# Colibri.net
KiCad netlist of a schematic drawn in Altium Designer
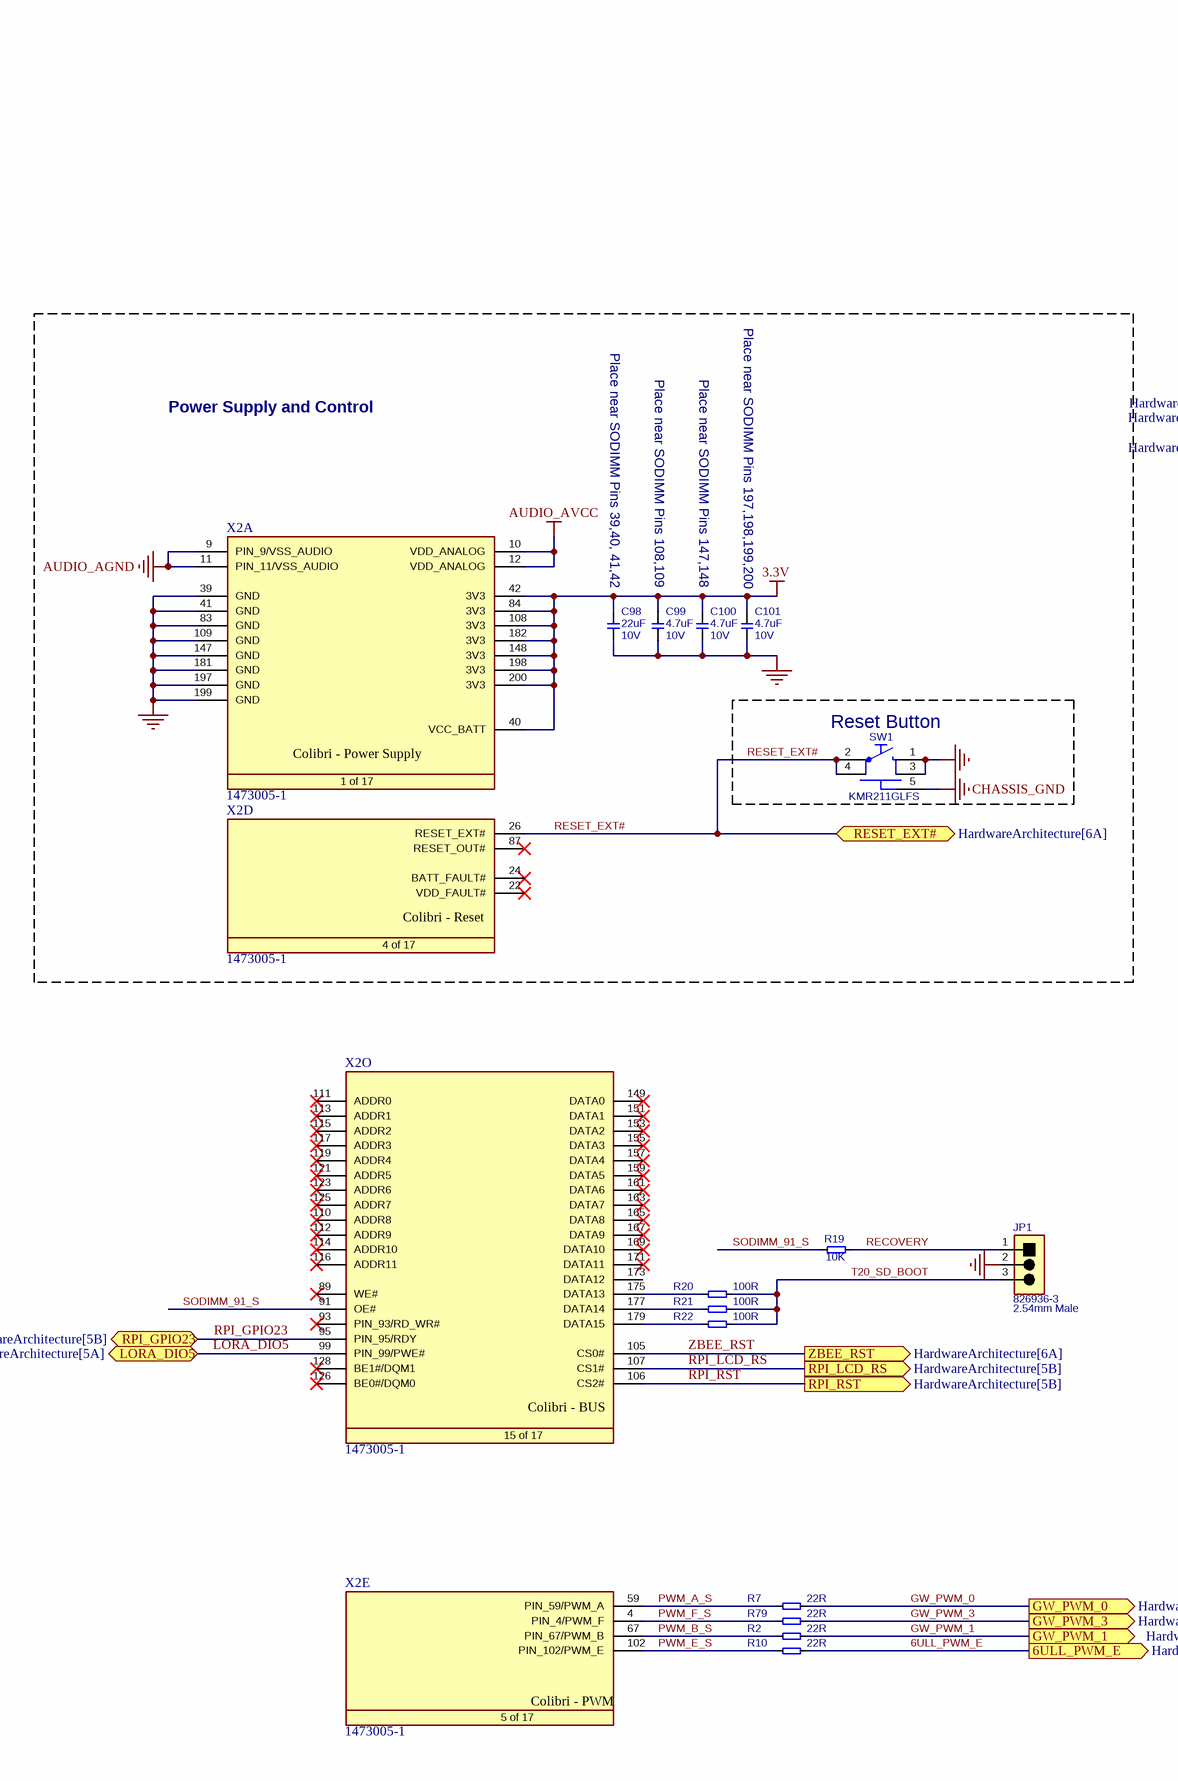
[diagram p0: Colibri.SchDoc, left]
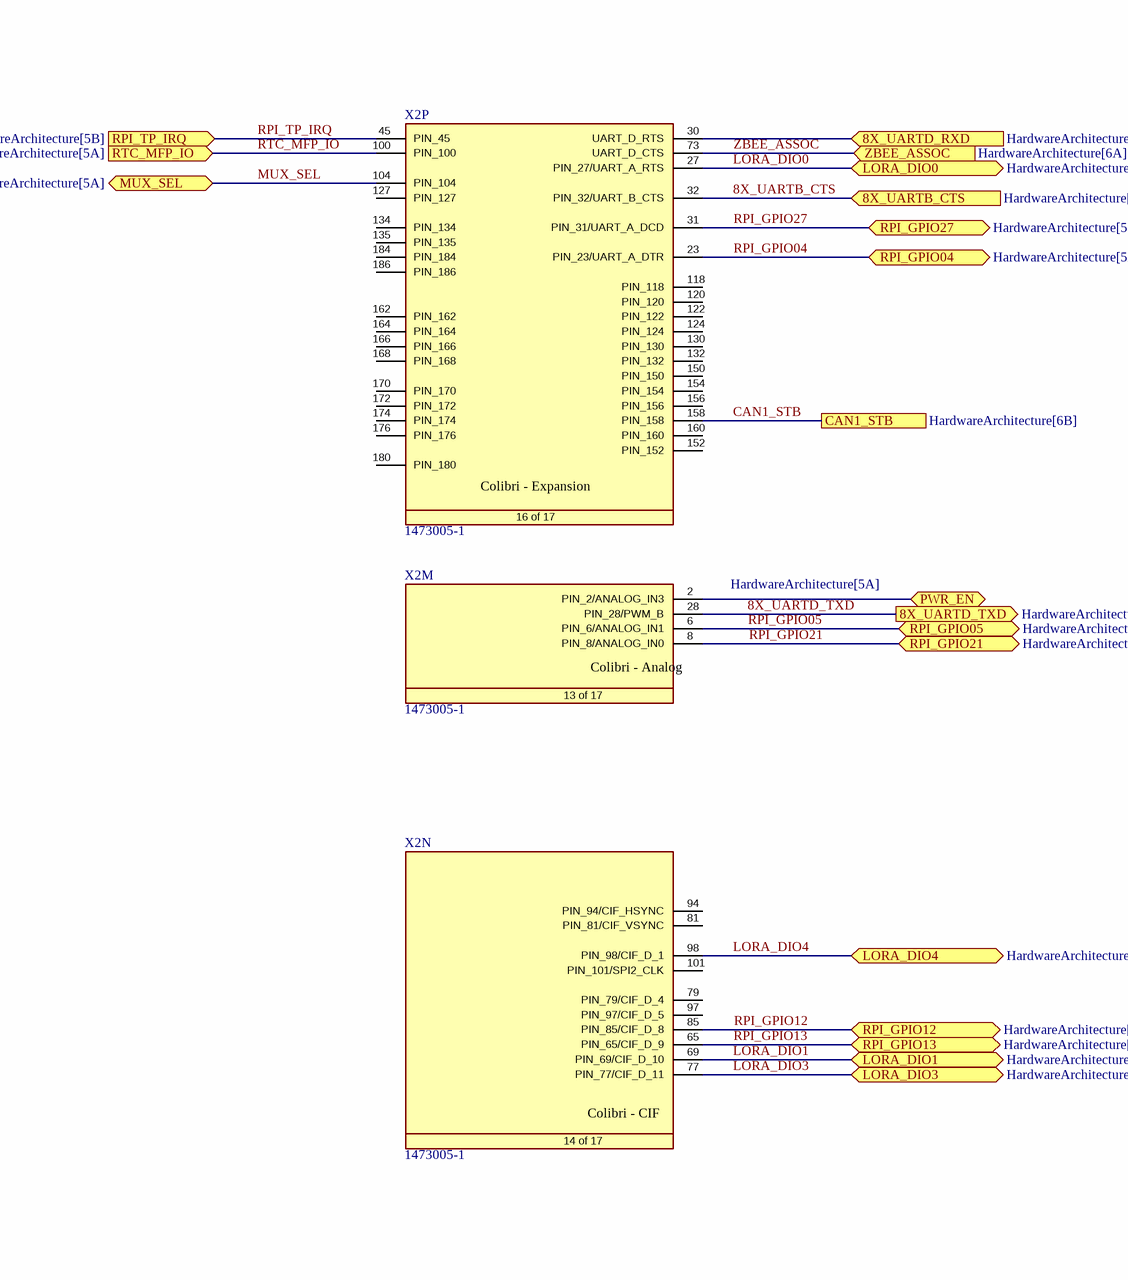
[diagram p1: Colibri.SchDoc, right]

(export (version "E")
  (design (tool "Eeschema 10.0.6"))
  (components
    (comp (ref "C98")
      (value "22uF")
      (footprint "T_CAPC0805X125N")
      (description "Capacitor Ceramic X5R 22uF 10V 20% 0805")
      (fields (field (name "TOLERANCE") "20%") (field (name "RATING") "10V"))
      (libsource (lib "Iris") (part "C-X5R-22uF-10V-20%-0805"))
    )
    (comp (ref "C99")
      (value "4.7uF")
      (footprint "T_CAPC0603X33N")
      (description "Capacitor Ceramic X5R 4.7uF 10V 10% 0603")
      (fields (field (name "TOLERANCE") "10%") (field (name "RATING") "10V"))
      (libsource (lib "Iris") (part "C-X5R-4.7uF-10V-10%-0603"))
    )
    (comp (ref "C100")
      (value "4.7uF")
      (footprint "T_CAPC0603X33N")
      (description "Capacitor Ceramic X5R 4.7uF 10V 10% 0603")
      (fields (field (name "TOLERANCE") "10%") (field (name "RATING") "10V"))
      (libsource (lib "Iris") (part "C-X5R-4.7uF-10V-10%-0603"))
    )
    (comp (ref "C101")
      (value "4.7uF")
      (footprint "T_CAPC0603X33N")
      (description "Capacitor Ceramic X5R 4.7uF 10V 10% 0603")
      (fields (field (name "TOLERANCE") "10%") (field (name "RATING") "10V"))
      (libsource (lib "Iris") (part "C-X5R-4.7uF-10V-10%-0603"))
    )
    (comp (ref "JP1")
      (value "826936-3")
      (footprint "T_TYCO_826936-3")
      (description "Jumper, 3-Pin")
      (fields (field (name "MANUFACTURER PART NO.") "826936-3"))
      (libsource (lib "Iris") (part "CON-Tyco-826936-3-1X3-2.54mm-JP"))
    )
    (comp (ref "R2")
      (value "22R")
      (footprint "RESC1005X40N")
      (description "Resistor 22 ohm 63mW 5% 0402")
      (fields (field (name "TOLERANCE") "5%"))
      (libsource (lib "Iris") (part "R-22R-63mW-5%-0402"))
    )
    (comp (ref "R7")
      (value "22R")
      (footprint "RESC1005X40N")
      (description "Resistor 22 ohm 63mW 5% 0402")
      (fields (field (name "TOLERANCE") "5%"))
      (libsource (lib "Iris") (part "R-22R-63mW-5%-0402"))
    )
    (comp (ref "R10")
      (value "22R")
      (footprint "RESC1005X40N")
      (description "Resistor 22 ohm 63mW 5% 0402")
      (fields (field (name "TOLERANCE") "5%"))
      (libsource (lib "Iris") (part "R-22R-63mW-5%-0402"))
    )
    (comp (ref "R19")
      (value "10K")
      (footprint "RESC1005X40N")
      (description "Resistor 10 Kohm 63mW 1% 0402")
      (fields (field (name "TOLERANCE") "1%"))
      (libsource (lib "Iris") (part "R-10KR-63mW-1%-0402"))
    )
    (comp (ref "R20")
      (value "100R")
      (footprint "T_RESC0603X30N")
      (description "Resistor 100 ohm 63mW 5% 0603")
      (fields (field (name "TOLERANCE") "5%"))
      (libsource (lib "Iris") (part "R-100R-63mW-5%-0603"))
    )
    (comp (ref "R21")
      (value "100R")
      (footprint "T_RESC0603X30N")
      (description "Resistor 100 ohm 63mW 5% 0603")
      (fields (field (name "TOLERANCE") "5%"))
      (libsource (lib "Iris") (part "R-100R-63mW-5%-0603"))
    )
    (comp (ref "R22")
      (value "100R")
      (footprint "T_RESC0603X30N")
      (description "Resistor 100 ohm 63mW 5% 0603")
      (fields (field (name "TOLERANCE") "5%"))
      (libsource (lib "Iris") (part "R-100R-63mW-5%-0603"))
    )
    (comp (ref "R79")
      (value "22R")
      (footprint "RESC1005X40N")
      (description "Resistor 22 ohm 63mW 5% 0402")
      (fields (field (name "TOLERANCE") "5%"))
      (libsource (lib "Iris") (part "R-22R-63mW-5%-0402"))
    )
    (comp (ref "SW1")
      (value "KMR211GLFS")
      (footprint "T_CnK_KMR211GLFS")
      (description "Power ON Switch")
      (libsource (lib "Iris") (part "SW_CnK-KMR211GLFS-1VA"))
    )
    (comp (ref "X2")
      (value "1473005-1")
      (footprint "T_Tyco_1473005-1")
      (description "SODIMM Connector")
      (fields (field (name "MANUFACTURER PART NO.") "1473005-1"))
      (libsource (lib "Iris") (part "CON-Tyco-1473005-1-200-0.6mm"))
    )
  )
  (nets
    (net (code "1") (name "/6ULL_PWM_E") (class "Default")
      (node (ref "R10") (pin "2") (pinfunction "2_2") (pintype "passive"))
    )
    (net (code "2") (name "/8X_UARTB_CTS") (class "Default")
      (node (ref "X2") (pin "32") (pinfunction "PIN_32/UART_B_CTS_32") (pintype "passive"))
    )
    (net (code "3") (name "/8X_UARTD_RXD") (class "Default")
      (node (ref "X2") (pin "30") (pinfunction "UART_D_RTS_30") (pintype "passive"))
    )
    (net (code "4") (name "/8X_UARTD_TXD") (class "Default")
      (node (ref "X2") (pin "28") (pinfunction "PIN_28/PWM_B_28") (pintype "passive"))
    )
    (net (code "5") (name "/CAN1_STB") (class "Default")
      (node (ref "X2") (pin "158") (pinfunction "PIN_158_158") (pintype "passive"))
    )
    (net (code "6") (name "/GW_PWM_0") (class "Default")
      (node (ref "R7") (pin "2") (pinfunction "2_2") (pintype "passive"))
    )
    (net (code "7") (name "/GW_PWM_1") (class "Default")
      (node (ref "R2") (pin "2") (pinfunction "2_2") (pintype "passive"))
    )
    (net (code "8") (name "/GW_PWM_3") (class "Default")
      (node (ref "R79") (pin "2") (pinfunction "2_2") (pintype "passive"))
    )
    (net (code "9") (name "/LORA_DIO0") (class "Default")
      (node (ref "X2") (pin "27") (pinfunction "PIN_27/UART_A_RTS_27") (pintype "passive"))
    )
    (net (code "10") (name "/LORA_DIO1") (class "Default")
      (node (ref "X2") (pin "69") (pinfunction "PIN_69/CIF_D_10_69") (pintype "passive"))
    )
    (net (code "11") (name "/LORA_DIO3") (class "Default")
      (node (ref "X2") (pin "77") (pinfunction "PIN_77/CIF_D_11_77") (pintype "passive"))
    )
    (net (code "12") (name "/LORA_DIO4") (class "Default")
      (node (ref "X2") (pin "98") (pinfunction "PIN_98/CIF_D_1_98") (pintype "passive"))
    )
    (net (code "13") (name "/LORA_DIO5") (class "Default")
      (node (ref "X2") (pin "99") (pinfunction "PIN_99/PWE#_99") (pintype "passive"))
    )
    (net (code "14") (name "/MUX_SEL") (class "Default")
      (node (ref "X2") (pin "104") (pinfunction "PIN_104_104") (pintype "passive"))
    )
    (net (code "15") (name "/PWM_A_S") (class "Default")
      (node (ref "R7") (pin "1") (pinfunction "1_1") (pintype "passive"))
      (node (ref "X2") (pin "59") (pinfunction "PIN_59/PWM_A_59") (pintype "passive"))
    )
    (net (code "16") (name "/PWM_B_S") (class "Default")
      (node (ref "R2") (pin "1") (pinfunction "1_1") (pintype "passive"))
      (node (ref "X2") (pin "67") (pinfunction "PIN_67/PWM_B_67") (pintype "passive"))
    )
    (net (code "17") (name "/PWM_E_S") (class "Default")
      (node (ref "R10") (pin "1") (pinfunction "1_1") (pintype "passive"))
      (node (ref "X2") (pin "102") (pinfunction "PIN_102/PWM_E_102") (pintype "passive"))
    )
    (net (code "18") (name "/PWM_F_S") (class "Default")
      (node (ref "R79") (pin "1") (pinfunction "1_1") (pintype "passive"))
      (node (ref "X2") (pin "4") (pinfunction "PIN_4/PWM_F_4") (pintype "passive"))
    )
    (net (code "19") (name "/PWR_EN") (class "Default")
      (node (ref "X2") (pin "2") (pinfunction "PIN_2/ANALOG_IN3_2") (pintype "passive"))
    )
    (net (code "20") (name "/RECOVERY") (class "Default")
      (node (ref "JP1") (pin "1") (pinfunction "1_1") (pintype "passive"))
      (node (ref "R19") (pin "2") (pinfunction "2_2") (pintype "passive"))
    )
    (net (code "21") (name "/RESET_EXT#") (class "Default")
      (node (ref "SW1") (pin "2") (pinfunction "2_2") (pintype "passive"))
      (node (ref "SW1") (pin "4") (pinfunction "4_4") (pintype "passive"))
      (node (ref "X2") (pin "26") (pinfunction "RESET_EXT#_26") (pintype "passive"))
    )
    (net (code "22") (name "/RPI_GPIO04") (class "Default")
      (node (ref "X2") (pin "23") (pinfunction "PIN_23/UART_A_DTR_23") (pintype "passive"))
    )
    (net (code "23") (name "/RPI_GPIO05") (class "Default")
      (node (ref "X2") (pin "6") (pinfunction "PIN_6/ANALOG_IN1_6") (pintype "passive"))
    )
    (net (code "24") (name "/RPI_GPIO12") (class "Default")
      (node (ref "X2") (pin "85") (pinfunction "PIN_85/CIF_D_8_85") (pintype "passive"))
    )
    (net (code "25") (name "/RPI_GPIO13") (class "Default")
      (node (ref "X2") (pin "65") (pinfunction "PIN_65/CIF_D_9_65") (pintype "passive"))
    )
    (net (code "26") (name "/RPI_GPIO21") (class "Default")
      (node (ref "X2") (pin "8") (pinfunction "PIN_8/ANALOG_IN0_8") (pintype "passive"))
    )
    (net (code "27") (name "/RPI_GPIO23") (class "Default")
      (node (ref "X2") (pin "95") (pinfunction "PIN_95/RDY_95") (pintype "passive"))
    )
    (net (code "28") (name "/RPI_GPIO27") (class "Default")
      (node (ref "X2") (pin "31") (pinfunction "PIN_31/UART_A_DCD_31") (pintype "passive"))
    )
    (net (code "29") (name "/RPI_LCD_RS") (class "Default")
      (node (ref "X2") (pin "107") (pinfunction "CS1#_107") (pintype "passive"))
    )
    (net (code "30") (name "/RPI_RST") (class "Default")
      (node (ref "X2") (pin "106") (pinfunction "CS2#_106") (pintype "passive"))
    )
    (net (code "31") (name "/RPI_TP_IRQ") (class "Default")
      (node (ref "X2") (pin "45") (pinfunction "PIN_45_45") (pintype "passive"))
    )
    (net (code "32") (name "/RTC_MFP_IO") (class "Default")
      (node (ref "X2") (pin "100") (pinfunction "PIN_100_100") (pintype "passive"))
    )
    (net (code "33") (name "/SODIMM_91_S") (class "Default")
      (node (ref "R19") (pin "1") (pinfunction "1_1") (pintype "passive"))
      (node (ref "X2") (pin "91") (pinfunction "OE#_91") (pintype "passive"))
    )
    (net (code "34") (name "/T20_SD_BOOT") (class "Default")
      (node (ref "JP1") (pin "3") (pinfunction "3_3") (pintype "passive"))
      (node (ref "R20") (pin "1") (pinfunction "1_1") (pintype "passive"))
      (node (ref "R21") (pin "1") (pinfunction "1_1") (pintype "passive"))
      (node (ref "R22") (pin "1") (pinfunction "1_1") (pintype "passive"))
    )
    (net (code "35") (name "/ZBEE_ASSOC") (class "Default")
      (node (ref "X2") (pin "73") (pinfunction "UART_D_CTS_73") (pintype "passive"))
    )
    (net (code "36") (name "/ZBEE_RST") (class "Default")
      (node (ref "X2") (pin "105") (pinfunction "CS0#_105") (pintype "passive"))
    )
    (net (code "37") (name "3.3V") (class "Default")
      (node (ref "C100") (pin "1") (pinfunction "1_1") (pintype "passive"))
      (node (ref "C101") (pin "1") (pinfunction "1_1") (pintype "passive"))
      (node (ref "C98") (pin "2") (pinfunction "2_2") (pintype "passive"))
      (node (ref "C99") (pin "1") (pinfunction "1_1") (pintype "passive"))
      (node (ref "X2") (pin "108") (pinfunction "3V3_108") (pintype "passive"))
      (node (ref "X2") (pin "148") (pinfunction "3V3_148") (pintype "passive"))
      (node (ref "X2") (pin "182") (pinfunction "3V3_182") (pintype "power_in"))
      (node (ref "X2") (pin "198") (pinfunction "3V3_198") (pintype "power_in"))
      (node (ref "X2") (pin "200") (pinfunction "3V3_200") (pintype "power_in"))
      (node (ref "X2") (pin "40") (pinfunction "VCC_BATT_40") (pintype "power_in"))
      (node (ref "X2") (pin "42") (pinfunction "3V3_42") (pintype "power_in"))
      (node (ref "X2") (pin "84") (pinfunction "3V3_84") (pintype "power_in"))
    )
    (net (code "38") (name "AUDIO_AGND") (class "Default")
      (node (ref "X2") (pin "11") (pinfunction "PIN_11/VSS_AUDIO_11") (pintype "passive"))
      (node (ref "X2") (pin "9") (pinfunction "PIN_9/VSS_AUDIO_9") (pintype "passive"))
    )
    (net (code "39") (name "AUDIO_AVCC") (class "Default")
      (node (ref "X2") (pin "10") (pinfunction "VDD_ANALOG_10") (pintype "passive"))
      (node (ref "X2") (pin "12") (pinfunction "VDD_ANALOG_12") (pintype "passive"))
    )
    (net (code "40") (name "CHASSIS_GND") (class "Default")
      (node (ref "SW1") (pin "5") (pinfunction "5_5") (pintype "passive"))
    )
    (net (code "41") (name "GND") (class "Default")
      (node (ref "C100") (pin "2") (pinfunction "2_2") (pintype "passive"))
      (node (ref "C101") (pin "2") (pinfunction "2_2") (pintype "passive"))
      (node (ref "C98") (pin "1") (pinfunction "1_1") (pintype "passive"))
      (node (ref "C99") (pin "2") (pinfunction "2_2") (pintype "passive"))
      (node (ref "JP1") (pin "2") (pinfunction "2_2") (pintype "passive"))
      (node (ref "SW1") (pin "1") (pinfunction "1_1") (pintype "passive"))
      (node (ref "SW1") (pin "3") (pinfunction "3_3") (pintype "passive"))
      (node (ref "X2") (pin "109") (pinfunction "GND_109") (pintype "power_in"))
      (node (ref "X2") (pin "147") (pinfunction "GND_147") (pintype "power_in"))
      (node (ref "X2") (pin "181") (pinfunction "GND_181") (pintype "power_in"))
      (node (ref "X2") (pin "197") (pinfunction "GND_197") (pintype "power_in"))
      (node (ref "X2") (pin "199") (pinfunction "GND_199") (pintype "power_in"))
      (node (ref "X2") (pin "39") (pinfunction "GND_39") (pintype "power_in"))
      (node (ref "X2") (pin "41") (pinfunction "GND_41") (pintype "power_in"))
      (node (ref "X2") (pin "83") (pinfunction "GND_83") (pintype "power_in"))
    )
    (net (code "42") (name "Net-(X2O-DATA13)") (class "Default")
      (node (ref "R20") (pin "2") (pinfunction "2_2") (pintype "passive"))
      (node (ref "X2") (pin "175") (pinfunction "DATA13_175") (pintype "passive"))
    )
    (net (code "43") (name "Net-(X2O-DATA14)") (class "Default")
      (node (ref "R21") (pin "2") (pinfunction "2_2") (pintype "passive"))
      (node (ref "X2") (pin "177") (pinfunction "DATA14_177") (pintype "passive"))
    )
    (net (code "44") (name "Net-(X2O-DATA15)") (class "Default")
      (node (ref "R22") (pin "2") (pinfunction "2_2") (pintype "passive"))
      (node (ref "X2") (pin "179") (pinfunction "DATA15_179") (pintype "passive"))
    )
    (net (code "45") (name "unconnected-(X2D-BATT_FAULT#-Pad24)") (class "Default")
      (node (ref "X2") (pin "24") (pinfunction "BATT_FAULT#_24") (pintype "passive+no_connect"))
    )
    (net (code "46") (name "unconnected-(X2D-RESET_OUT#-Pad87)") (class "Default")
      (node (ref "X2") (pin "87") (pinfunction "RESET_OUT#_87") (pintype "passive+no_connect"))
    )
    (net (code "47") (name "unconnected-(X2D-VDD_FAULT#-Pad22)") (class "Default")
      (node (ref "X2") (pin "22") (pinfunction "VDD_FAULT#_22") (pintype "passive+no_connect"))
    )
    (net (code "48") (name "unconnected-(X2N-PIN_79{slash}CIF_D_4-Pad79)") (class "Default")
      (node (ref "X2") (pin "79") (pinfunction "PIN_79/CIF_D_4_79") (pintype "passive"))
    )
    (net (code "49") (name "unconnected-(X2N-PIN_81{slash}CIF_VSYNC-Pad81)") (class "Default")
      (node (ref "X2") (pin "81") (pinfunction "PIN_81/CIF_VSYNC_81") (pintype "passive"))
    )
    (net (code "50") (name "unconnected-(X2N-PIN_94{slash}CIF_HSYNC-Pad94)") (class "Default")
      (node (ref "X2") (pin "94") (pinfunction "PIN_94/CIF_HSYNC_94") (pintype "passive"))
    )
    (net (code "51") (name "unconnected-(X2N-PIN_97{slash}CIF_D_5-Pad97)") (class "Default")
      (node (ref "X2") (pin "97") (pinfunction "PIN_97/CIF_D_5_97") (pintype "passive"))
    )
    (net (code "52") (name "unconnected-(X2N-PIN_101{slash}SPI2_CLK-Pad101)") (class "Default")
      (node (ref "X2") (pin "101") (pinfunction "PIN_101/SPI2_CLK_101") (pintype "passive"))
    )
    (net (code "53") (name "unconnected-(X2O-ADDR0-Pad111)") (class "Default")
      (node (ref "X2") (pin "111") (pinfunction "ADDR0_111") (pintype "passive+no_connect"))
    )
    (net (code "54") (name "unconnected-(X2O-ADDR1-Pad113)") (class "Default")
      (node (ref "X2") (pin "113") (pinfunction "ADDR1_113") (pintype "passive+no_connect"))
    )
    (net (code "55") (name "unconnected-(X2O-ADDR2-Pad115)") (class "Default")
      (node (ref "X2") (pin "115") (pinfunction "ADDR2_115") (pintype "passive+no_connect"))
    )
    (net (code "56") (name "unconnected-(X2O-ADDR3-Pad117)") (class "Default")
      (node (ref "X2") (pin "117") (pinfunction "ADDR3_117") (pintype "passive+no_connect"))
    )
    (net (code "57") (name "unconnected-(X2O-ADDR4-Pad119)") (class "Default")
      (node (ref "X2") (pin "119") (pinfunction "ADDR4_119") (pintype "passive+no_connect"))
    )
    (net (code "58") (name "unconnected-(X2O-ADDR5-Pad121)") (class "Default")
      (node (ref "X2") (pin "121") (pinfunction "ADDR5_121") (pintype "passive+no_connect"))
    )
    (net (code "59") (name "unconnected-(X2O-ADDR6-Pad123)") (class "Default")
      (node (ref "X2") (pin "123") (pinfunction "ADDR6_123") (pintype "passive+no_connect"))
    )
    (net (code "60") (name "unconnected-(X2O-ADDR7-Pad125)") (class "Default")
      (node (ref "X2") (pin "125") (pinfunction "ADDR7_125") (pintype "passive+no_connect"))
    )
    (net (code "61") (name "unconnected-(X2O-ADDR8-Pad110)") (class "Default")
      (node (ref "X2") (pin "110") (pinfunction "ADDR8_110") (pintype "passive+no_connect"))
    )
    (net (code "62") (name "unconnected-(X2O-ADDR9-Pad112)") (class "Default")
      (node (ref "X2") (pin "112") (pinfunction "ADDR9_112") (pintype "passive+no_connect"))
    )
    (net (code "63") (name "unconnected-(X2O-ADDR10-Pad114)") (class "Default")
      (node (ref "X2") (pin "114") (pinfunction "ADDR10_114") (pintype "passive+no_connect"))
    )
    (net (code "64") (name "unconnected-(X2O-ADDR11-Pad116)") (class "Default")
      (node (ref "X2") (pin "116") (pinfunction "ADDR11_116") (pintype "passive+no_connect"))
    )
    (net (code "65") (name "unconnected-(X2O-BE0#{slash}DQM0-Pad126)") (class "Default")
      (node (ref "X2") (pin "126") (pinfunction "BE0#/DQM0_126") (pintype "passive+no_connect"))
    )
    (net (code "66") (name "unconnected-(X2O-BE1#{slash}DQM1-Pad128)") (class "Default")
      (node (ref "X2") (pin "128") (pinfunction "BE1#/DQM1_128") (pintype "passive+no_connect"))
    )
    (net (code "67") (name "unconnected-(X2O-DATA0-Pad149)") (class "Default")
      (node (ref "X2") (pin "149") (pinfunction "DATA0_149") (pintype "passive+no_connect"))
    )
    (net (code "68") (name "unconnected-(X2O-DATA1-Pad151)") (class "Default")
      (node (ref "X2") (pin "151") (pinfunction "DATA1_151") (pintype "passive+no_connect"))
    )
    (net (code "69") (name "unconnected-(X2O-DATA2-Pad153)") (class "Default")
      (node (ref "X2") (pin "153") (pinfunction "DATA2_153") (pintype "passive+no_connect"))
    )
    (net (code "70") (name "unconnected-(X2O-DATA3-Pad155)") (class "Default")
      (node (ref "X2") (pin "155") (pinfunction "DATA3_155") (pintype "passive+no_connect"))
    )
    (net (code "71") (name "unconnected-(X2O-DATA4-Pad157)") (class "Default")
      (node (ref "X2") (pin "157") (pinfunction "DATA4_157") (pintype "passive+no_connect"))
    )
    (net (code "72") (name "unconnected-(X2O-DATA5-Pad159)") (class "Default")
      (node (ref "X2") (pin "159") (pinfunction "DATA5_159") (pintype "passive+no_connect"))
    )
    (net (code "73") (name "unconnected-(X2O-DATA6-Pad161)") (class "Default")
      (node (ref "X2") (pin "161") (pinfunction "DATA6_161") (pintype "passive+no_connect"))
    )
    (net (code "74") (name "unconnected-(X2O-DATA7-Pad163)") (class "Default")
      (node (ref "X2") (pin "163") (pinfunction "DATA7_163") (pintype "passive+no_connect"))
    )
    (net (code "75") (name "unconnected-(X2O-DATA8-Pad165)") (class "Default")
      (node (ref "X2") (pin "165") (pinfunction "DATA8_165") (pintype "passive+no_connect"))
    )
    (net (code "76") (name "unconnected-(X2O-DATA9-Pad167)") (class "Default")
      (node (ref "X2") (pin "167") (pinfunction "DATA9_167") (pintype "passive+no_connect"))
    )
    (net (code "77") (name "unconnected-(X2O-DATA10-Pad169)") (class "Default")
      (node (ref "X2") (pin "169") (pinfunction "DATA10_169") (pintype "passive+no_connect"))
    )
    (net (code "78") (name "unconnected-(X2O-DATA11-Pad171)") (class "Default")
      (node (ref "X2") (pin "171") (pinfunction "DATA11_171") (pintype "passive+no_connect"))
    )
    (net (code "79") (name "unconnected-(X2O-DATA12-Pad173)") (class "Default")
      (node (ref "X2") (pin "173") (pinfunction "DATA12_173") (pintype "passive"))
    )
    (net (code "80") (name "unconnected-(X2O-PIN_93{slash}RD_WR#-Pad93)") (class "Default")
      (node (ref "X2") (pin "93") (pinfunction "PIN_93/RD_WR#_93") (pintype "passive+no_connect"))
    )
    (net (code "81") (name "unconnected-(X2O-WE#-Pad89)") (class "Default")
      (node (ref "X2") (pin "89") (pinfunction "WE#_89") (pintype "passive+no_connect"))
    )
    (net (code "82") (name "unconnected-(X2P-PIN_118-Pad118)") (class "Default")
      (node (ref "X2") (pin "118") (pinfunction "PIN_118_118") (pintype "passive"))
    )
    (net (code "83") (name "unconnected-(X2P-PIN_120-Pad120)") (class "Default")
      (node (ref "X2") (pin "120") (pinfunction "PIN_120_120") (pintype "passive"))
    )
    (net (code "84") (name "unconnected-(X2P-PIN_122-Pad122)") (class "Default")
      (node (ref "X2") (pin "122") (pinfunction "PIN_122_122") (pintype "passive"))
    )
    (net (code "85") (name "unconnected-(X2P-PIN_124-Pad124)") (class "Default")
      (node (ref "X2") (pin "124") (pinfunction "PIN_124_124") (pintype "passive"))
    )
    (net (code "86") (name "unconnected-(X2P-PIN_127-Pad127)") (class "Default")
      (node (ref "X2") (pin "127") (pinfunction "PIN_127_127") (pintype "passive"))
    )
    (net (code "87") (name "unconnected-(X2P-PIN_130-Pad130)") (class "Default")
      (node (ref "X2") (pin "130") (pinfunction "PIN_130_130") (pintype "passive"))
    )
    (net (code "88") (name "unconnected-(X2P-PIN_132-Pad132)") (class "Default")
      (node (ref "X2") (pin "132") (pinfunction "PIN_132_132") (pintype "passive"))
    )
    (net (code "89") (name "unconnected-(X2P-PIN_134-Pad134)") (class "Default")
      (node (ref "X2") (pin "134") (pinfunction "PIN_134_134") (pintype "passive"))
    )
    (net (code "90") (name "unconnected-(X2P-PIN_135-Pad135)") (class "Default")
      (node (ref "X2") (pin "135") (pinfunction "PIN_135_135") (pintype "passive"))
    )
    (net (code "91") (name "unconnected-(X2P-PIN_150-Pad150)") (class "Default")
      (node (ref "X2") (pin "150") (pinfunction "PIN_150_150") (pintype "passive"))
    )
    (net (code "92") (name "unconnected-(X2P-PIN_152-Pad152)") (class "Default")
      (node (ref "X2") (pin "152") (pinfunction "PIN_152_152") (pintype "passive"))
    )
    (net (code "93") (name "unconnected-(X2P-PIN_154-Pad154)") (class "Default")
      (node (ref "X2") (pin "154") (pinfunction "PIN_154_154") (pintype "passive"))
    )
    (net (code "94") (name "unconnected-(X2P-PIN_156-Pad156)") (class "Default")
      (node (ref "X2") (pin "156") (pinfunction "PIN_156_156") (pintype "passive"))
    )
    (net (code "95") (name "unconnected-(X2P-PIN_160-Pad160)") (class "Default")
      (node (ref "X2") (pin "160") (pinfunction "PIN_160_160") (pintype "passive"))
    )
    (net (code "96") (name "unconnected-(X2P-PIN_162-Pad162)") (class "Default")
      (node (ref "X2") (pin "162") (pinfunction "PIN_162_162") (pintype "passive"))
    )
    (net (code "97") (name "unconnected-(X2P-PIN_164-Pad164)") (class "Default")
      (node (ref "X2") (pin "164") (pinfunction "PIN_164_164") (pintype "passive"))
    )
    (net (code "98") (name "unconnected-(X2P-PIN_166-Pad166)") (class "Default")
      (node (ref "X2") (pin "166") (pinfunction "PIN_166_166") (pintype "passive"))
    )
    (net (code "99") (name "unconnected-(X2P-PIN_168-Pad168)") (class "Default")
      (node (ref "X2") (pin "168") (pinfunction "PIN_168_168") (pintype "passive"))
    )
    (net (code "100") (name "unconnected-(X2P-PIN_170-Pad170)") (class "Default")
      (node (ref "X2") (pin "170") (pinfunction "PIN_170_170") (pintype "passive"))
    )
    (net (code "101") (name "unconnected-(X2P-PIN_172-Pad172)") (class "Default")
      (node (ref "X2") (pin "172") (pinfunction "PIN_172_172") (pintype "passive"))
    )
    (net (code "102") (name "unconnected-(X2P-PIN_174-Pad174)") (class "Default")
      (node (ref "X2") (pin "174") (pinfunction "PIN_174_174") (pintype "passive"))
    )
    (net (code "103") (name "unconnected-(X2P-PIN_176-Pad176)") (class "Default")
      (node (ref "X2") (pin "176") (pinfunction "PIN_176_176") (pintype "passive"))
    )
    (net (code "104") (name "unconnected-(X2P-PIN_180-Pad180)") (class "Default")
      (node (ref "X2") (pin "180") (pinfunction "PIN_180_180") (pintype "passive"))
    )
    (net (code "105") (name "unconnected-(X2P-PIN_184-Pad184)") (class "Default")
      (node (ref "X2") (pin "184") (pinfunction "PIN_184_184") (pintype "passive"))
    )
    (net (code "106") (name "unconnected-(X2P-PIN_186-Pad186)") (class "Default")
      (node (ref "X2") (pin "186") (pinfunction "PIN_186_186") (pintype "passive"))
    )
  )
)
